# Comparator.net
KiCad netlist of a schematic drawn in Altium Designer
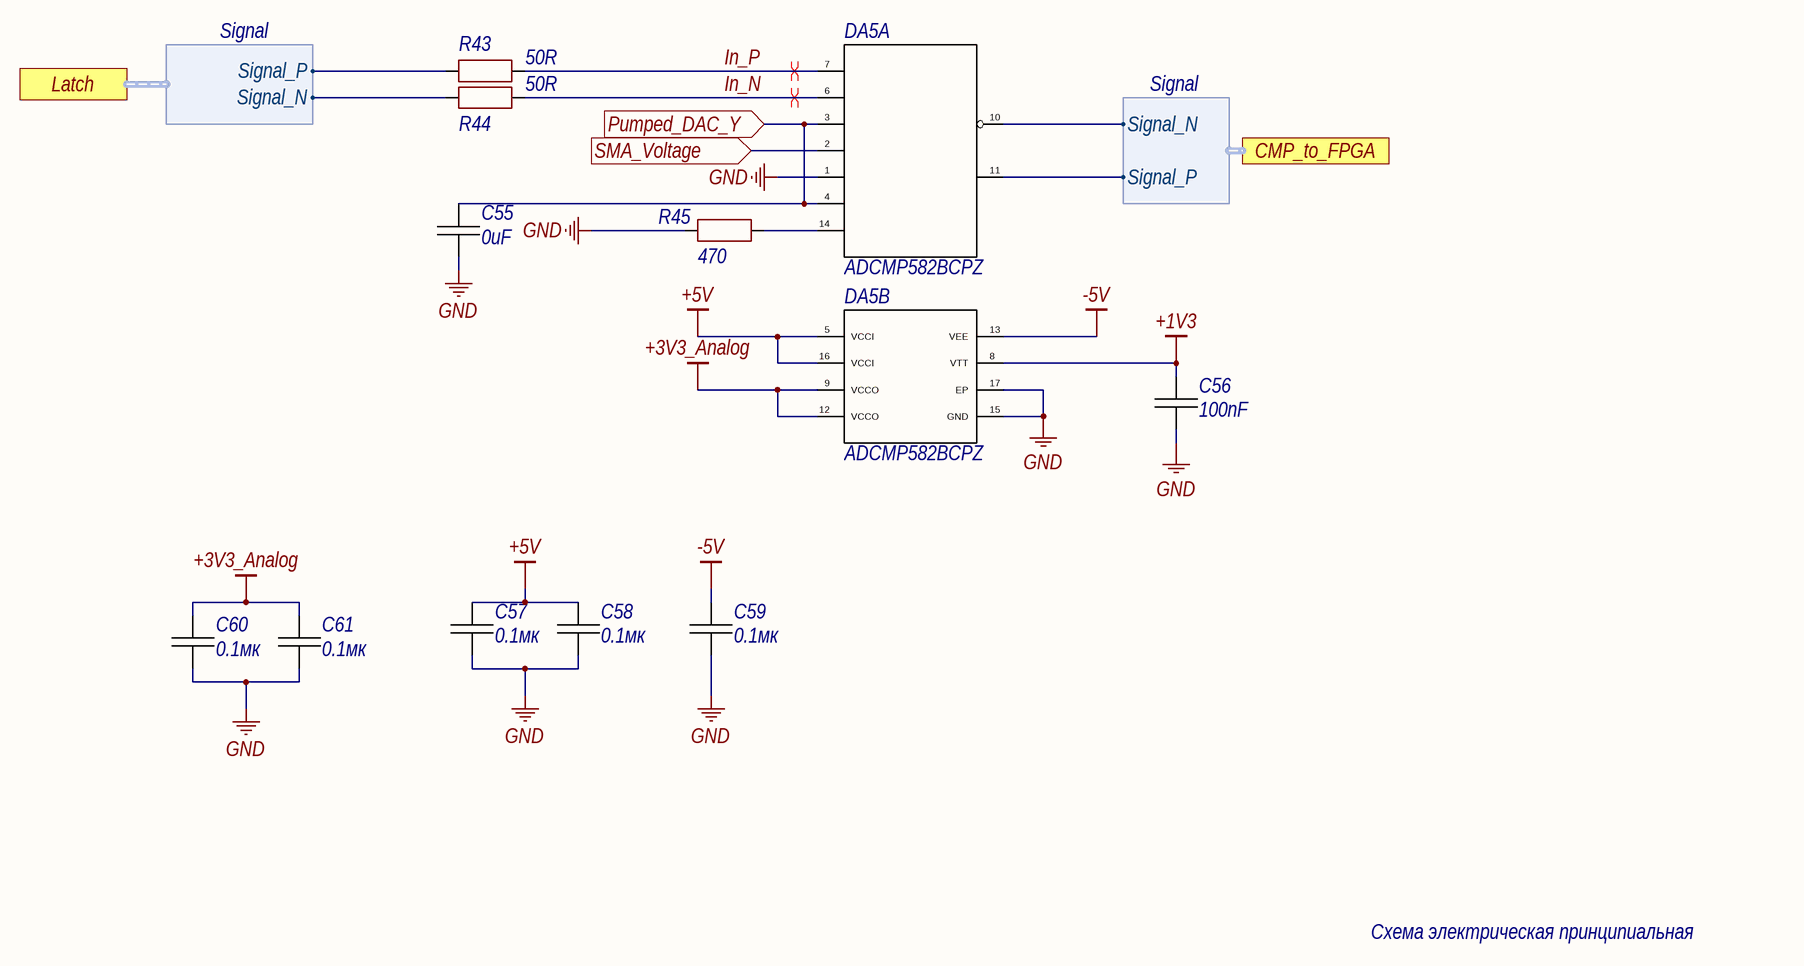
[diagram p0: Comparator.SchDoc]

(export (version "E")
  (design (tool "Eeschema 10.0.6"))
  (components
    (comp (ref "C55")
      (value "0uF")
      (footprint "CAP0402")
      (fields
        (field (name "MANUFACTURER") "Samsung Electro-Mechanics")
        (field (name "MPN") "CL05B104KB54PNC")
        (field (name "TOLERANCE") "10%")
      )
      (libsource (lib "Library") (part "CAPC"))
    )
    (comp (ref "C56")
      (value "100nF")
      (footprint "CAP0402")
      (fields
        (field (name "MANUFACTURER") "Samsung Electro-Mechanics")
        (field (name "MPN") "CL05B104KB54PNC")
        (field (name "TOLERANCE") "10%")
      )
      (libsource (lib "Library") (part "CAPC"))
    )
    (comp (ref "C57")
      (value "0.1мк")
      (footprint "CAP0402")
      (fields
        (field (name "MANUFACTURER") "Samsung Electro-Mechanics")
        (field (name "MPN") "CL05B104KB54PNC")
        (field (name "TOLERANCE") "10%")
      )
      (libsource (lib "Library") (part "CAPC"))
    )
    (comp (ref "C58")
      (value "0.1мк")
      (footprint "CAP0402")
      (fields
        (field (name "MANUFACTURER") "Samsung Electro-Mechanics")
        (field (name "MPN") "CL05B104KB54PNC")
        (field (name "TOLERANCE") "10%")
      )
      (libsource (lib "Library") (part "CAPC"))
    )
    (comp (ref "C59")
      (value "0.1мк")
      (footprint "CAP0402")
      (fields
        (field (name "MANUFACTURER") "Samsung Electro-Mechanics")
        (field (name "MPN") "CL05B104KB54PNC")
        (field (name "TOLERANCE") "10%")
      )
      (libsource (lib "Library") (part "CAPC"))
    )
    (comp (ref "C60")
      (value "0.1мк")
      (footprint "CAP0402")
      (fields
        (field (name "MANUFACTURER") "Samsung Electro-Mechanics")
        (field (name "MPN") "CL05B104KB54PNC")
        (field (name "TOLERANCE") "10%")
      )
      (libsource (lib "Library") (part "CAPC"))
    )
    (comp (ref "C61")
      (value "0.1мк")
      (footprint "CAP0402")
      (fields
        (field (name "MANUFACTURER") "Samsung Electro-Mechanics")
        (field (name "MPN") "CL05B104KB54PNC")
        (field (name "TOLERANCE") "10%")
      )
      (libsource (lib "Library") (part "CAPC"))
    )
    (comp (ref "DA5")
      (value "~")
      (footprint "ADI-CP-16-3_N")
      (description "Ultrafast SiGe Voltage Comparator, + / - 5 V, 180 ps Delay, Industrial, 16-pin QFN (CP-16-3), Reel")
      (fields
        (field (name "MPN") "ADCMP582BCPZ")
        (field (name "PART NUMBER") "ADCMP582BCPZ")
        (field (name "MANUFACTURER") "AD")
      )
      (libsource (lib "Library") (part "ADCMP582BCPZ"))
    )
    (comp (ref "R43")
      (value "50R")
      (footprint "RESC0402(1005)_M")
      (fields (field (name "PART NUMBER") "RES0402") (field (name "Comment") "50R "))
      (libsource (lib "Library") (part "RES"))
    )
    (comp (ref "R44")
      (value "50R")
      (footprint "RESC0402(1005)_M")
      (fields (field (name "PART NUMBER") "RES0402") (field (name "Comment") "50R "))
      (libsource (lib "Library") (part "RES"))
    )
    (comp (ref "R45")
      (value "470")
      (footprint "RESC0402(1005)_M")
      (fields
        (field (name "MANUFACTURER") "UNI-ROYAL(Uniroyal Elec)")
        (field (name "MPN") "0402WGF4700TCE")
        (field (name "TOLERANCE") "1%")
      )
      (libsource (lib "") (part "RES_1"))
    )
  )
  (nets
    (net (code "2") (name "+1V3") (class "Default")
      (node (ref "C56") (pin "2") (pinfunction "2_2") (pintype "passive"))
      (node (ref "DA5") (pin "8") (pinfunction "VTT_8") (pintype "power_in"))
    )
    (net (code "3") (name "+3V3_Analog") (class "Default")
      (node (ref "C60") (pin "1") (pinfunction "1_1") (pintype "passive"))
      (node (ref "C61") (pin "1") (pinfunction "1_1") (pintype "passive"))
      (node (ref "DA5") (pin "12") (pinfunction "VCCO_12") (pintype "power_in"))
      (node (ref "DA5") (pin "9") (pinfunction "VCCO_9") (pintype "power_in"))
    )
    (net (code "4") (name "+5V") (class "Default")
      (node (ref "C57") (pin "1") (pinfunction "1_1") (pintype "passive"))
      (node (ref "C58") (pin "1") (pinfunction "1_1") (pintype "passive"))
      (node (ref "DA5") (pin "16") (pinfunction "VCCI_16") (pintype "power_in"))
      (node (ref "DA5") (pin "5") (pinfunction "VCCI_5") (pintype "power_in"))
    )
    (net (code "5") (name "-5V") (class "Default")
      (node (ref "C59") (pin "1") (pinfunction "1_1") (pintype "passive"))
      (node (ref "DA5") (pin "13") (pinfunction "VEE_13") (pintype "power_in"))
    )
    (net (code "6") (name "/In_N") (class "Default")
      (node (ref "DA5") (pin "6") (pinfunction "~{LE}_6") (pintype "passive"))
      (node (ref "R44") (pin "1") (pinfunction "1_1") (pintype "passive"))
    )
    (net (code "7") (name "/In_P") (class "Default")
      (node (ref "DA5") (pin "7") (pinfunction "LE_7") (pintype "passive"))
      (node (ref "R43") (pin "1") (pinfunction "1_1") (pintype "passive"))
    )
    (net (code "8") (name "/Pumped_DAC_Y") (class "Default")
      (node (ref "C55") (pin "1") (pinfunction "1_1") (pintype "passive"))
      (node (ref "DA5") (pin "3") (pinfunction "VN_3") (pintype "passive"))
      (node (ref "DA5") (pin "4") (pinfunction "VTN_4") (pintype "passive"))
    )
    (net (code "9") (name "/SMA_Voltage") (class "Default")
      (node (ref "DA5") (pin "2") (pinfunction "VP_2") (pintype "passive"))
    )
    (net (code "11") (name "GND") (class "Default")
      (node (ref "C55") (pin "2") (pinfunction "2_2") (pintype "passive"))
      (node (ref "C56") (pin "1") (pinfunction "1_1") (pintype "passive"))
      (node (ref "C57") (pin "2") (pinfunction "2_2") (pintype "passive"))
      (node (ref "C58") (pin "2") (pinfunction "2_2") (pintype "passive"))
      (node (ref "C59") (pin "2") (pinfunction "2_2") (pintype "passive"))
      (node (ref "C60") (pin "2") (pinfunction "2_2") (pintype "passive"))
      (node (ref "C61") (pin "2") (pinfunction "2_2") (pintype "passive"))
      (node (ref "DA5") (pin "1") (pinfunction "VTP_1") (pintype "passive"))
      (node (ref "DA5") (pin "15") (pinfunction "GND_15") (pintype "power_in"))
      (node (ref "DA5") (pin "17") (pinfunction "EP_17") (pintype "passive"))
      (node (ref "R45") (pin "1") (pinfunction "1_1") (pintype "passive"))
    )
    (net (code "12") (name "Net-(DA5A-HYS)") (class "Default")
      (node (ref "DA5") (pin "14") (pinfunction "HYS_14") (pintype "passive"))
      (node (ref "R45") (pin "2") (pinfunction "2_2") (pintype "passive"))
    )
    (net (code "13") (name "unconnected-(DA5A-Q-Pad11)") (class "Default")
      (node (ref "DA5") (pin "11") (pinfunction "Q_11") (pintype "passive"))
    )
    (net (code "14") (name "unconnected-(DA5A-~{Q}-Pad10)") (class "Default")
      (node (ref "DA5") (pin "10") (pinfunction "~{Q}_10") (pintype "passive"))
    )
    (net (code "15") (name "unconnected-(R43-Pad2)") (class "Default")
      (node (ref "R43") (pin "2") (pinfunction "2_2") (pintype "passive"))
    )
    (net (code "16") (name "unconnected-(R44-Pad2)") (class "Default")
      (node (ref "R44") (pin "2") (pinfunction "2_2") (pintype "passive"))
    )
  )
)
